# Control.net
KiCad netlist of a schematic drawn in Altium Designer
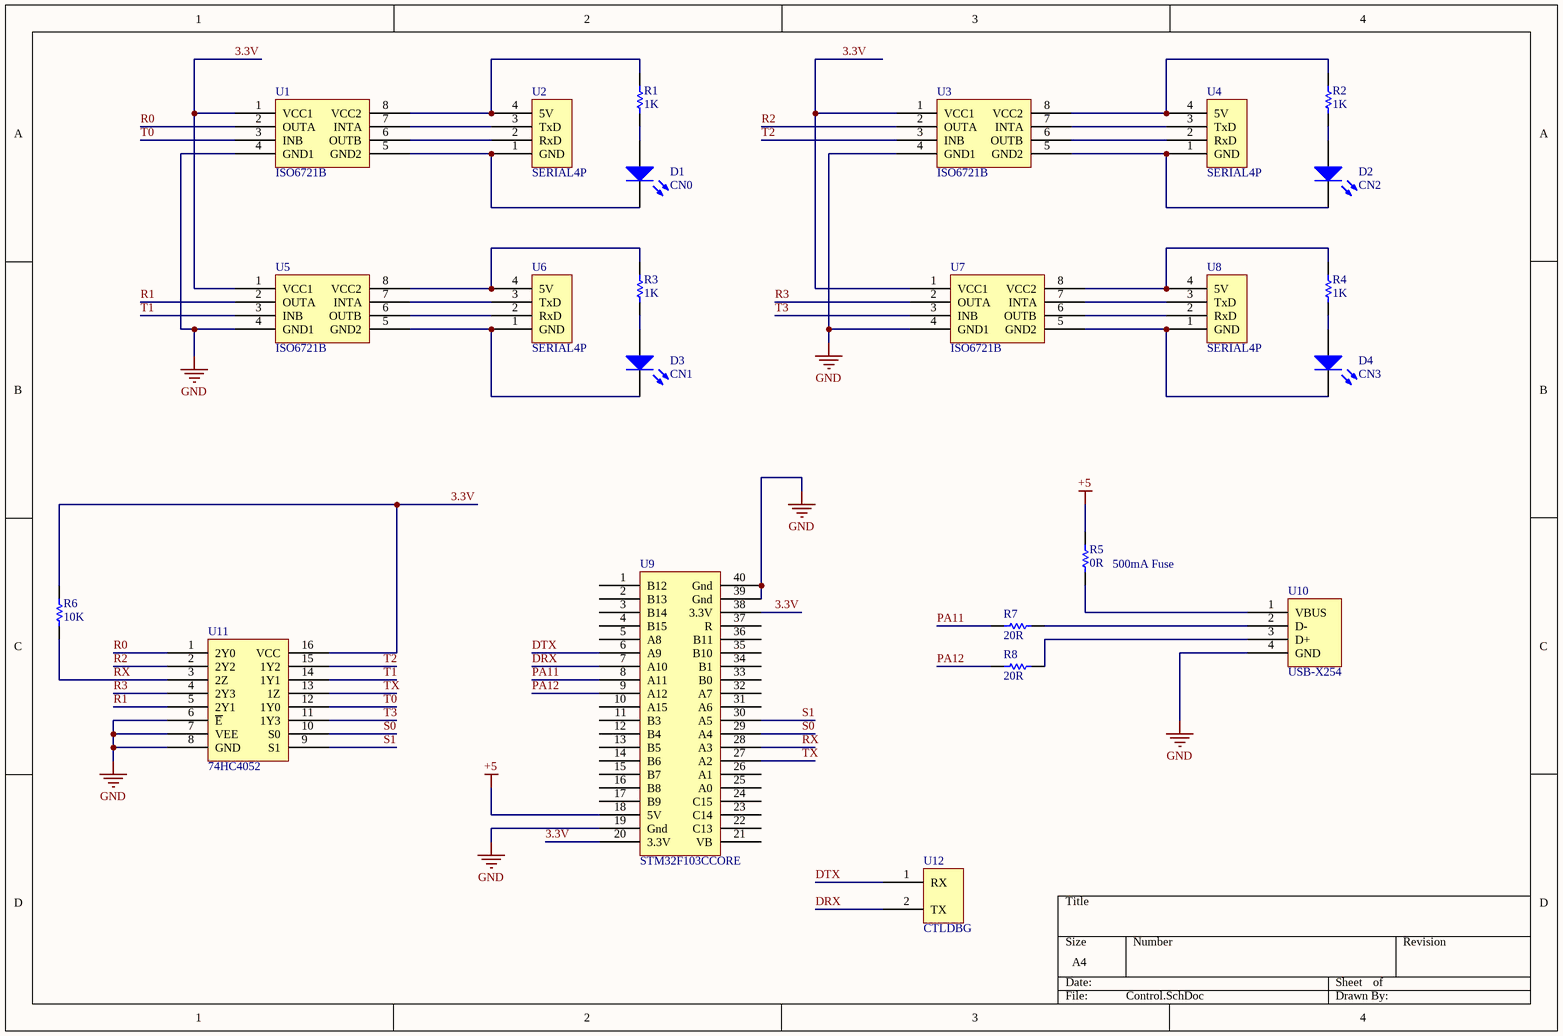
[diagram p0: Control.SchDoc]

(export (version "E")
  (design (tool "Eeschema 10.0.6"))
  (components
    (comp (ref "D1")
      (value "CN0")
      (footprint "CNCPowerSupply:LED")
      (description "Typical RED GaAs LED")
      (fields (field (name "PUBLISHER") "Altium Limited"))
      (libsource (lib "Miscellaneous Devices") (part "LED1"))
    )
    (comp (ref "D2")
      (value "CN2")
      (footprint "CNCPowerSupply:LED")
      (description "Typical RED GaAs LED")
      (fields (field (name "PUBLISHER") "Altium Limited"))
      (libsource (lib "Miscellaneous Devices") (part "LED1"))
    )
    (comp (ref "D3")
      (value "CN1")
      (footprint "CNCPowerSupply:LED")
      (description "Typical RED GaAs LED")
      (fields (field (name "PUBLISHER") "Altium Limited"))
      (libsource (lib "Miscellaneous Devices") (part "LED1"))
    )
    (comp (ref "D4")
      (value "CN3")
      (footprint "CNCPowerSupply:LED")
      (description "Typical RED GaAs LED")
      (fields (field (name "PUBLISHER") "Altium Limited"))
      (libsource (lib "Miscellaneous Devices") (part "LED1"))
    )
    (comp (ref "R1")
      (value "1K")
      (footprint "CNCPowerSupply:RESC1608L")
      (description "Resistor")
      (fields (field (name "PUBLISHER") "Altium Limited"))
      (libsource (lib "Miscellaneous Devices") (part "Res1"))
    )
    (comp (ref "R2")
      (value "1K")
      (footprint "CNCPowerSupply:RESC1608L")
      (description "Resistor")
      (fields (field (name "PUBLISHER") "Altium Limited"))
      (libsource (lib "Miscellaneous Devices") (part "Res1"))
    )
    (comp (ref "R3")
      (value "1K")
      (footprint "CNCPowerSupply:RESC1608L")
      (description "Resistor")
      (fields (field (name "PUBLISHER") "Altium Limited"))
      (libsource (lib "Miscellaneous Devices") (part "Res1"))
    )
    (comp (ref "R4")
      (value "1K")
      (footprint "CNCPowerSupply:RESC1608L")
      (description "Resistor")
      (fields (field (name "PUBLISHER") "Altium Limited"))
      (libsource (lib "Miscellaneous Devices") (part "Res1"))
    )
    (comp (ref "R5")
      (value "500mA Fuse")
      (footprint "CNCPowerSupply:RESC3216L")
      (description "Resistor")
      (fields (field (name "ALTIUM_VALUE") "0R") (field (name "PUBLISHER") "Altium Limited"))
      (libsource (lib "Miscellaneous Devices") (part "Res1"))
    )
    (comp (ref "R6")
      (value "10K")
      (footprint "CNCPowerSupply:RESC1608L")
      (description "Resistor")
      (fields (field (name "PUBLISHER") "Altium Limited"))
      (libsource (lib "Miscellaneous Devices") (part "Res1"))
    )
    (comp (ref "R7")
      (value "20R")
      (footprint "CNCPowerSupply:RESC1608L")
      (description "Resistor")
      (fields (field (name "PUBLISHER") "Altium Limited"))
      (libsource (lib "Miscellaneous Devices") (part "Res1"))
    )
    (comp (ref "R8")
      (value "20R")
      (footprint "CNCPowerSupply:RESC1608L")
      (description "Resistor")
      (fields (field (name "PUBLISHER") "Altium Limited"))
      (libsource (lib "Miscellaneous Devices") (part "Res1"))
    )
    (comp (ref "U1")
      (value "ISO6721B")
      (footprint "CNCPowerSupply:SOP127P636-8L")
      (libsource (lib "CNCPowerSupply") (part "ISO6721B"))
    )
    (comp (ref "U2")
      (value "SERIAL4P")
      (footprint "CNCPowerSupply:X254-4P")
      (libsource (lib "CNCPowerSupply") (part "SERIAL4P"))
    )
    (comp (ref "U3")
      (value "ISO6721B")
      (footprint "CNCPowerSupply:SOP127P636-8L")
      (libsource (lib "CNCPowerSupply") (part "ISO6721B"))
    )
    (comp (ref "U4")
      (value "SERIAL4P")
      (footprint "CNCPowerSupply:X254-4P")
      (libsource (lib "CNCPowerSupply") (part "SERIAL4P"))
    )
    (comp (ref "U5")
      (value "ISO6721B")
      (footprint "CNCPowerSupply:SOP127P636-8L")
      (libsource (lib "CNCPowerSupply") (part "ISO6721B"))
    )
    (comp (ref "U6")
      (value "SERIAL4P")
      (footprint "CNCPowerSupply:X254-4P")
      (libsource (lib "CNCPowerSupply") (part "SERIAL4P"))
    )
    (comp (ref "U7")
      (value "ISO6721B")
      (footprint "CNCPowerSupply:SOP127P636-8L")
      (libsource (lib "CNCPowerSupply") (part "ISO6721B"))
    )
    (comp (ref "U8")
      (value "SERIAL4P")
      (footprint "CNCPowerSupply:X254-4P")
      (libsource (lib "CNCPowerSupply") (part "SERIAL4P"))
    )
    (comp (ref "U9")
      (value "STM32F103CCORE")
      (footprint "CNCPowerSupply:STM32F103C")
      (libsource (lib "CNCPowerSupply") (part "STM32F103CCORE"))
    )
    (comp (ref "U10")
      (value "USB-X254")
      (footprint "X254-4P")
      (libsource (lib "CNCPowerSupply") (part "USB-X254"))
    )
    (comp (ref "U11")
      (value "74HC4052")
      (footprint "CNCPowerSupply:SOP127P762-16L")
      (libsource (lib "CNCPowerSupply") (part "74HC4052"))
    )
    (comp (ref "U12")
      (value "CTLDBG")
      (footprint "CNCPowerSupply:CTLDBG")
      (libsource (lib "CNCPowerSupply") (part "CTLDBG"))
    )
  )
  (nets
    (net (code "1") (name "+5") (class "Default")
      (node (ref "R5") (pin "2") (pinfunction "2_2") (pintype "passive"))
      (node (ref "U9") (pin "18") (pinfunction "5V_18") (pintype "passive"))
    )
    (net (code "2") (name "/3.3V") (class "Default")
      (node (ref "R6") (pin "2") (pinfunction "2_2") (pintype "passive"))
      (node (ref "U1") (pin "1") (pinfunction "VCC1_1") (pintype "passive"))
      (node (ref "U11") (pin "16") (pinfunction "VCC_16") (pintype "passive"))
      (node (ref "U3") (pin "1") (pinfunction "VCC1_1") (pintype "passive"))
      (node (ref "U5") (pin "1") (pinfunction "VCC1_1") (pintype "passive"))
      (node (ref "U7") (pin "1") (pinfunction "VCC1_1") (pintype "passive"))
      (node (ref "U9") (pin "20") (pinfunction "3.3V_20") (pintype "passive"))
      (node (ref "U9") (pin "38") (pinfunction "3.3V_38") (pintype "passive"))
    )
    (net (code "3") (name "/DRX") (class "Default")
      (node (ref "U12") (pin "2") (pinfunction "TX_2") (pintype "passive"))
      (node (ref "U9") (pin "7") (pinfunction "A10_7") (pintype "passive"))
    )
    (net (code "4") (name "/DTX") (class "Default")
      (node (ref "U12") (pin "1") (pinfunction "RX_1") (pintype "passive"))
      (node (ref "U9") (pin "6") (pinfunction "A9_6") (pintype "passive"))
    )
    (net (code "5") (name "/PA11") (class "Default")
      (node (ref "R7") (pin "1") (pinfunction "1_1") (pintype "passive"))
      (node (ref "U9") (pin "8") (pinfunction "A11_8") (pintype "passive"))
    )
    (net (code "6") (name "/PA12") (class "Default")
      (node (ref "R8") (pin "1") (pinfunction "1_1") (pintype "passive"))
      (node (ref "U9") (pin "9") (pinfunction "A12_9") (pintype "passive"))
    )
    (net (code "7") (name "/R0") (class "Default")
      (node (ref "U1") (pin "2") (pinfunction "OUTA_2") (pintype "passive"))
      (node (ref "U11") (pin "1") (pinfunction "2Y0_1") (pintype "passive"))
    )
    (net (code "8") (name "/R1") (class "Default")
      (node (ref "U11") (pin "5") (pinfunction "2Y1_5") (pintype "passive"))
      (node (ref "U5") (pin "2") (pinfunction "OUTA_2") (pintype "passive"))
    )
    (net (code "9") (name "/R2") (class "Default")
      (node (ref "U11") (pin "2") (pinfunction "2Y2_2") (pintype "passive"))
      (node (ref "U3") (pin "2") (pinfunction "OUTA_2") (pintype "passive"))
    )
    (net (code "10") (name "/R3") (class "Default")
      (node (ref "U11") (pin "4") (pinfunction "2Y3_4") (pintype "passive"))
      (node (ref "U7") (pin "2") (pinfunction "OUTA_2") (pintype "passive"))
    )
    (net (code "11") (name "/RX") (class "Default")
      (node (ref "R6") (pin "1") (pinfunction "1_1") (pintype "passive"))
      (node (ref "U11") (pin "3") (pinfunction "2Z_3") (pintype "passive"))
      (node (ref "U9") (pin "28") (pinfunction "A3_28") (pintype "passive"))
    )
    (net (code "12") (name "/S0") (class "Default")
      (node (ref "U11") (pin "10") (pinfunction "S0_10") (pintype "passive"))
      (node (ref "U9") (pin "29") (pinfunction "A4_29") (pintype "passive"))
    )
    (net (code "13") (name "/S1") (class "Default")
      (node (ref "U11") (pin "9") (pinfunction "S1_9") (pintype "passive"))
      (node (ref "U9") (pin "30") (pinfunction "A5_30") (pintype "passive"))
    )
    (net (code "14") (name "/T0") (class "Default")
      (node (ref "U1") (pin "3") (pinfunction "INB_3") (pintype "passive"))
      (node (ref "U11") (pin "12") (pinfunction "1Y0_12") (pintype "passive"))
    )
    (net (code "15") (name "/T1") (class "Default")
      (node (ref "U11") (pin "14") (pinfunction "1Y1_14") (pintype "passive"))
      (node (ref "U5") (pin "3") (pinfunction "INB_3") (pintype "passive"))
    )
    (net (code "16") (name "/T2") (class "Default")
      (node (ref "U11") (pin "15") (pinfunction "1Y2_15") (pintype "passive"))
      (node (ref "U3") (pin "3") (pinfunction "INB_3") (pintype "passive"))
    )
    (net (code "17") (name "/T3") (class "Default")
      (node (ref "U11") (pin "11") (pinfunction "1Y3_11") (pintype "passive"))
      (node (ref "U7") (pin "3") (pinfunction "INB_3") (pintype "passive"))
    )
    (net (code "18") (name "/TX") (class "Default")
      (node (ref "U11") (pin "13") (pinfunction "1Z_13") (pintype "passive"))
      (node (ref "U9") (pin "27") (pinfunction "A2_27") (pintype "passive"))
    )
    (net (code "19") (name "GND") (class "Default")
      (node (ref "U1") (pin "4") (pinfunction "GND1_4") (pintype "passive"))
      (node (ref "U10") (pin "4") (pinfunction "GND_4") (pintype "passive"))
      (node (ref "U11") (pin "6") (pinfunction "~{E}_6") (pintype "passive"))
      (node (ref "U11") (pin "7") (pinfunction "VEE_7") (pintype "passive"))
      (node (ref "U11") (pin "8") (pinfunction "GND_8") (pintype "passive"))
      (node (ref "U3") (pin "4") (pinfunction "GND1_4") (pintype "passive"))
      (node (ref "U5") (pin "4") (pinfunction "GND1_4") (pintype "passive"))
      (node (ref "U7") (pin "4") (pinfunction "GND1_4") (pintype "passive"))
      (node (ref "U9") (pin "19") (pinfunction "Gnd_19") (pintype "passive"))
      (node (ref "U9") (pin "39") (pinfunction "Gnd_39") (pintype "passive"))
      (node (ref "U9") (pin "40") (pinfunction "Gnd_40") (pintype "passive"))
    )
    (net (code "20") (name "Net-(D1-A)") (class "Default")
      (node (ref "D1") (pin "1") (pinfunction "A_1") (pintype "passive"))
      (node (ref "R1") (pin "1") (pinfunction "1_1") (pintype "passive"))
    )
    (net (code "21") (name "Net-(D1-K)") (class "Default")
      (node (ref "D1") (pin "2") (pinfunction "K_2") (pintype "passive"))
      (node (ref "U1") (pin "5") (pinfunction "GND2_5") (pintype "passive"))
      (node (ref "U2") (pin "1") (pinfunction "GND_1") (pintype "passive"))
    )
    (net (code "22") (name "Net-(D2-A)") (class "Default")
      (node (ref "D2") (pin "1") (pinfunction "A_1") (pintype "passive"))
      (node (ref "R2") (pin "1") (pinfunction "1_1") (pintype "passive"))
    )
    (net (code "23") (name "Net-(D2-K)") (class "Default")
      (node (ref "D2") (pin "2") (pinfunction "K_2") (pintype "passive"))
      (node (ref "U3") (pin "5") (pinfunction "GND2_5") (pintype "passive"))
      (node (ref "U4") (pin "1") (pinfunction "GND_1") (pintype "passive"))
    )
    (net (code "24") (name "Net-(D3-A)") (class "Default")
      (node (ref "D3") (pin "1") (pinfunction "A_1") (pintype "passive"))
      (node (ref "R3") (pin "1") (pinfunction "1_1") (pintype "passive"))
    )
    (net (code "25") (name "Net-(D3-K)") (class "Default")
      (node (ref "D3") (pin "2") (pinfunction "K_2") (pintype "passive"))
      (node (ref "U5") (pin "5") (pinfunction "GND2_5") (pintype "passive"))
      (node (ref "U6") (pin "1") (pinfunction "GND_1") (pintype "passive"))
    )
    (net (code "26") (name "Net-(D4-A)") (class "Default")
      (node (ref "D4") (pin "1") (pinfunction "A_1") (pintype "passive"))
      (node (ref "R4") (pin "1") (pinfunction "1_1") (pintype "passive"))
    )
    (net (code "27") (name "Net-(D4-K)") (class "Default")
      (node (ref "D4") (pin "2") (pinfunction "K_2") (pintype "passive"))
      (node (ref "U7") (pin "5") (pinfunction "GND2_5") (pintype "passive"))
      (node (ref "U8") (pin "1") (pinfunction "GND_1") (pintype "passive"))
    )
    (net (code "28") (name "Net-(U1-INTA)") (class "Default")
      (node (ref "U1") (pin "7") (pinfunction "INTA_7") (pintype "passive"))
      (node (ref "U2") (pin "3") (pinfunction "TxD_3") (pintype "passive"))
    )
    (net (code "29") (name "Net-(U1-OUTB)") (class "Default")
      (node (ref "U1") (pin "6") (pinfunction "OUTB_6") (pintype "passive"))
      (node (ref "U2") (pin "2") (pinfunction "RxD_2") (pintype "passive"))
    )
    (net (code "30") (name "Net-(U1-VCC2)") (class "Default")
      (node (ref "R1") (pin "2") (pinfunction "2_2") (pintype "passive"))
      (node (ref "U1") (pin "8") (pinfunction "VCC2_8") (pintype "passive"))
      (node (ref "U2") (pin "4") (pinfunction "5V_4") (pintype "passive"))
    )
    (net (code "31") (name "Net-(U3-INTA)") (class "Default")
      (node (ref "U3") (pin "7") (pinfunction "INTA_7") (pintype "passive"))
      (node (ref "U4") (pin "3") (pinfunction "TxD_3") (pintype "passive"))
    )
    (net (code "32") (name "Net-(U3-OUTB)") (class "Default")
      (node (ref "U3") (pin "6") (pinfunction "OUTB_6") (pintype "passive"))
      (node (ref "U4") (pin "2") (pinfunction "RxD_2") (pintype "passive"))
    )
    (net (code "33") (name "Net-(U3-VCC2)") (class "Default")
      (node (ref "R2") (pin "2") (pinfunction "2_2") (pintype "passive"))
      (node (ref "U3") (pin "8") (pinfunction "VCC2_8") (pintype "passive"))
      (node (ref "U4") (pin "4") (pinfunction "5V_4") (pintype "passive"))
    )
    (net (code "34") (name "Net-(U5-INTA)") (class "Default")
      (node (ref "U5") (pin "7") (pinfunction "INTA_7") (pintype "passive"))
      (node (ref "U6") (pin "3") (pinfunction "TxD_3") (pintype "passive"))
    )
    (net (code "35") (name "Net-(U5-OUTB)") (class "Default")
      (node (ref "U5") (pin "6") (pinfunction "OUTB_6") (pintype "passive"))
      (node (ref "U6") (pin "2") (pinfunction "RxD_2") (pintype "passive"))
    )
    (net (code "36") (name "Net-(U5-VCC2)") (class "Default")
      (node (ref "R3") (pin "2") (pinfunction "2_2") (pintype "passive"))
      (node (ref "U5") (pin "8") (pinfunction "VCC2_8") (pintype "passive"))
      (node (ref "U6") (pin "4") (pinfunction "5V_4") (pintype "passive"))
    )
    (net (code "37") (name "Net-(U7-INTA)") (class "Default")
      (node (ref "U7") (pin "7") (pinfunction "INTA_7") (pintype "passive"))
      (node (ref "U8") (pin "3") (pinfunction "TxD_3") (pintype "passive"))
    )
    (net (code "38") (name "Net-(U7-OUTB)") (class "Default")
      (node (ref "U7") (pin "6") (pinfunction "OUTB_6") (pintype "passive"))
      (node (ref "U8") (pin "2") (pinfunction "RxD_2") (pintype "passive"))
    )
    (net (code "39") (name "Net-(U7-VCC2)") (class "Default")
      (node (ref "R4") (pin "2") (pinfunction "2_2") (pintype "passive"))
      (node (ref "U7") (pin "8") (pinfunction "VCC2_8") (pintype "passive"))
      (node (ref "U8") (pin "4") (pinfunction "5V_4") (pintype "passive"))
    )
    (net (code "40") (name "Net-(U10-D+)") (class "Default")
      (node (ref "R8") (pin "2") (pinfunction "2_2") (pintype "passive"))
      (node (ref "U10") (pin "3") (pinfunction "D+_3") (pintype "passive"))
    )
    (net (code "41") (name "Net-(U10-D-)") (class "Default")
      (node (ref "R7") (pin "2") (pinfunction "2_2") (pintype "passive"))
      (node (ref "U10") (pin "2") (pinfunction "D-_2") (pintype "passive"))
    )
    (net (code "42") (name "Net-(U10-VBUS)") (class "Default")
      (node (ref "R5") (pin "1") (pinfunction "1_1") (pintype "passive"))
      (node (ref "U10") (pin "1") (pinfunction "VBUS_1") (pintype "passive"))
    )
    (net (code "43") (name "unconnected-(U9-A0-Pad25)") (class "Default")
      (node (ref "U9") (pin "25") (pinfunction "A0_25") (pintype "passive"))
    )
    (net (code "44") (name "unconnected-(U9-A1-Pad26)") (class "Default")
      (node (ref "U9") (pin "26") (pinfunction "A1_26") (pintype "passive"))
    )
    (net (code "45") (name "unconnected-(U9-A6-Pad31)") (class "Default")
      (node (ref "U9") (pin "31") (pinfunction "A6_31") (pintype "passive"))
    )
    (net (code "46") (name "unconnected-(U9-A7-Pad32)") (class "Default")
      (node (ref "U9") (pin "32") (pinfunction "A7_32") (pintype "passive"))
    )
    (net (code "47") (name "unconnected-(U9-A8-Pad5)") (class "Default")
      (node (ref "U9") (pin "5") (pinfunction "A8_5") (pintype "passive"))
    )
    (net (code "48") (name "unconnected-(U9-A15-Pad10)") (class "Default")
      (node (ref "U9") (pin "10") (pinfunction "A15_10") (pintype "passive"))
    )
    (net (code "49") (name "unconnected-(U9-B0-Pad33)") (class "Default")
      (node (ref "U9") (pin "33") (pinfunction "B0_33") (pintype "passive"))
    )
    (net (code "50") (name "unconnected-(U9-B1-Pad34)") (class "Default")
      (node (ref "U9") (pin "34") (pinfunction "B1_34") (pintype "passive"))
    )
    (net (code "51") (name "unconnected-(U9-B3-Pad11)") (class "Default")
      (node (ref "U9") (pin "11") (pinfunction "B3_11") (pintype "passive"))
    )
    (net (code "52") (name "unconnected-(U9-B4-Pad12)") (class "Default")
      (node (ref "U9") (pin "12") (pinfunction "B4_12") (pintype "passive"))
    )
    (net (code "53") (name "unconnected-(U9-B5-Pad13)") (class "Default")
      (node (ref "U9") (pin "13") (pinfunction "B5_13") (pintype "passive"))
    )
    (net (code "54") (name "unconnected-(U9-B6-Pad14)") (class "Default")
      (node (ref "U9") (pin "14") (pinfunction "B6_14") (pintype "passive"))
    )
    (net (code "55") (name "unconnected-(U9-B7-Pad15)") (class "Default")
      (node (ref "U9") (pin "15") (pinfunction "B7_15") (pintype "passive"))
    )
    (net (code "56") (name "unconnected-(U9-B8-Pad16)") (class "Default")
      (node (ref "U9") (pin "16") (pinfunction "B8_16") (pintype "passive"))
    )
    (net (code "57") (name "unconnected-(U9-B9-Pad17)") (class "Default")
      (node (ref "U9") (pin "17") (pinfunction "B9_17") (pintype "passive"))
    )
    (net (code "58") (name "unconnected-(U9-B10-Pad35)") (class "Default")
      (node (ref "U9") (pin "35") (pinfunction "B10_35") (pintype "passive"))
    )
    (net (code "59") (name "unconnected-(U9-B11-Pad36)") (class "Default")
      (node (ref "U9") (pin "36") (pinfunction "B11_36") (pintype "passive"))
    )
    (net (code "60") (name "unconnected-(U9-B12-Pad1)") (class "Default")
      (node (ref "U9") (pin "1") (pinfunction "B12_1") (pintype "passive"))
    )
    (net (code "61") (name "unconnected-(U9-B13-Pad2)") (class "Default")
      (node (ref "U9") (pin "2") (pinfunction "B13_2") (pintype "passive"))
    )
    (net (code "62") (name "unconnected-(U9-B14-Pad3)") (class "Default")
      (node (ref "U9") (pin "3") (pinfunction "B14_3") (pintype "passive"))
    )
    (net (code "63") (name "unconnected-(U9-B15-Pad4)") (class "Default")
      (node (ref "U9") (pin "4") (pinfunction "B15_4") (pintype "passive"))
    )
    (net (code "64") (name "unconnected-(U9-C13-Pad22)") (class "Default")
      (node (ref "U9") (pin "22") (pinfunction "C13_22") (pintype "passive"))
    )
    (net (code "65") (name "unconnected-(U9-C14-Pad23)") (class "Default")
      (node (ref "U9") (pin "23") (pinfunction "C14_23") (pintype "passive"))
    )
    (net (code "66") (name "unconnected-(U9-C15-Pad24)") (class "Default")
      (node (ref "U9") (pin "24") (pinfunction "C15_24") (pintype "passive"))
    )
    (net (code "67") (name "unconnected-(U9-R-Pad37)") (class "Default")
      (node (ref "U9") (pin "37") (pinfunction "R_37") (pintype "passive"))
    )
    (net (code "68") (name "unconnected-(U9-VB-Pad21)") (class "Default")
      (node (ref "U9") (pin "21") (pinfunction "VB_21") (pintype "passive"))
    )
  )
)
